# 2_RS485_RS422.net
KiCad netlist of a schematic drawn in EAGLE
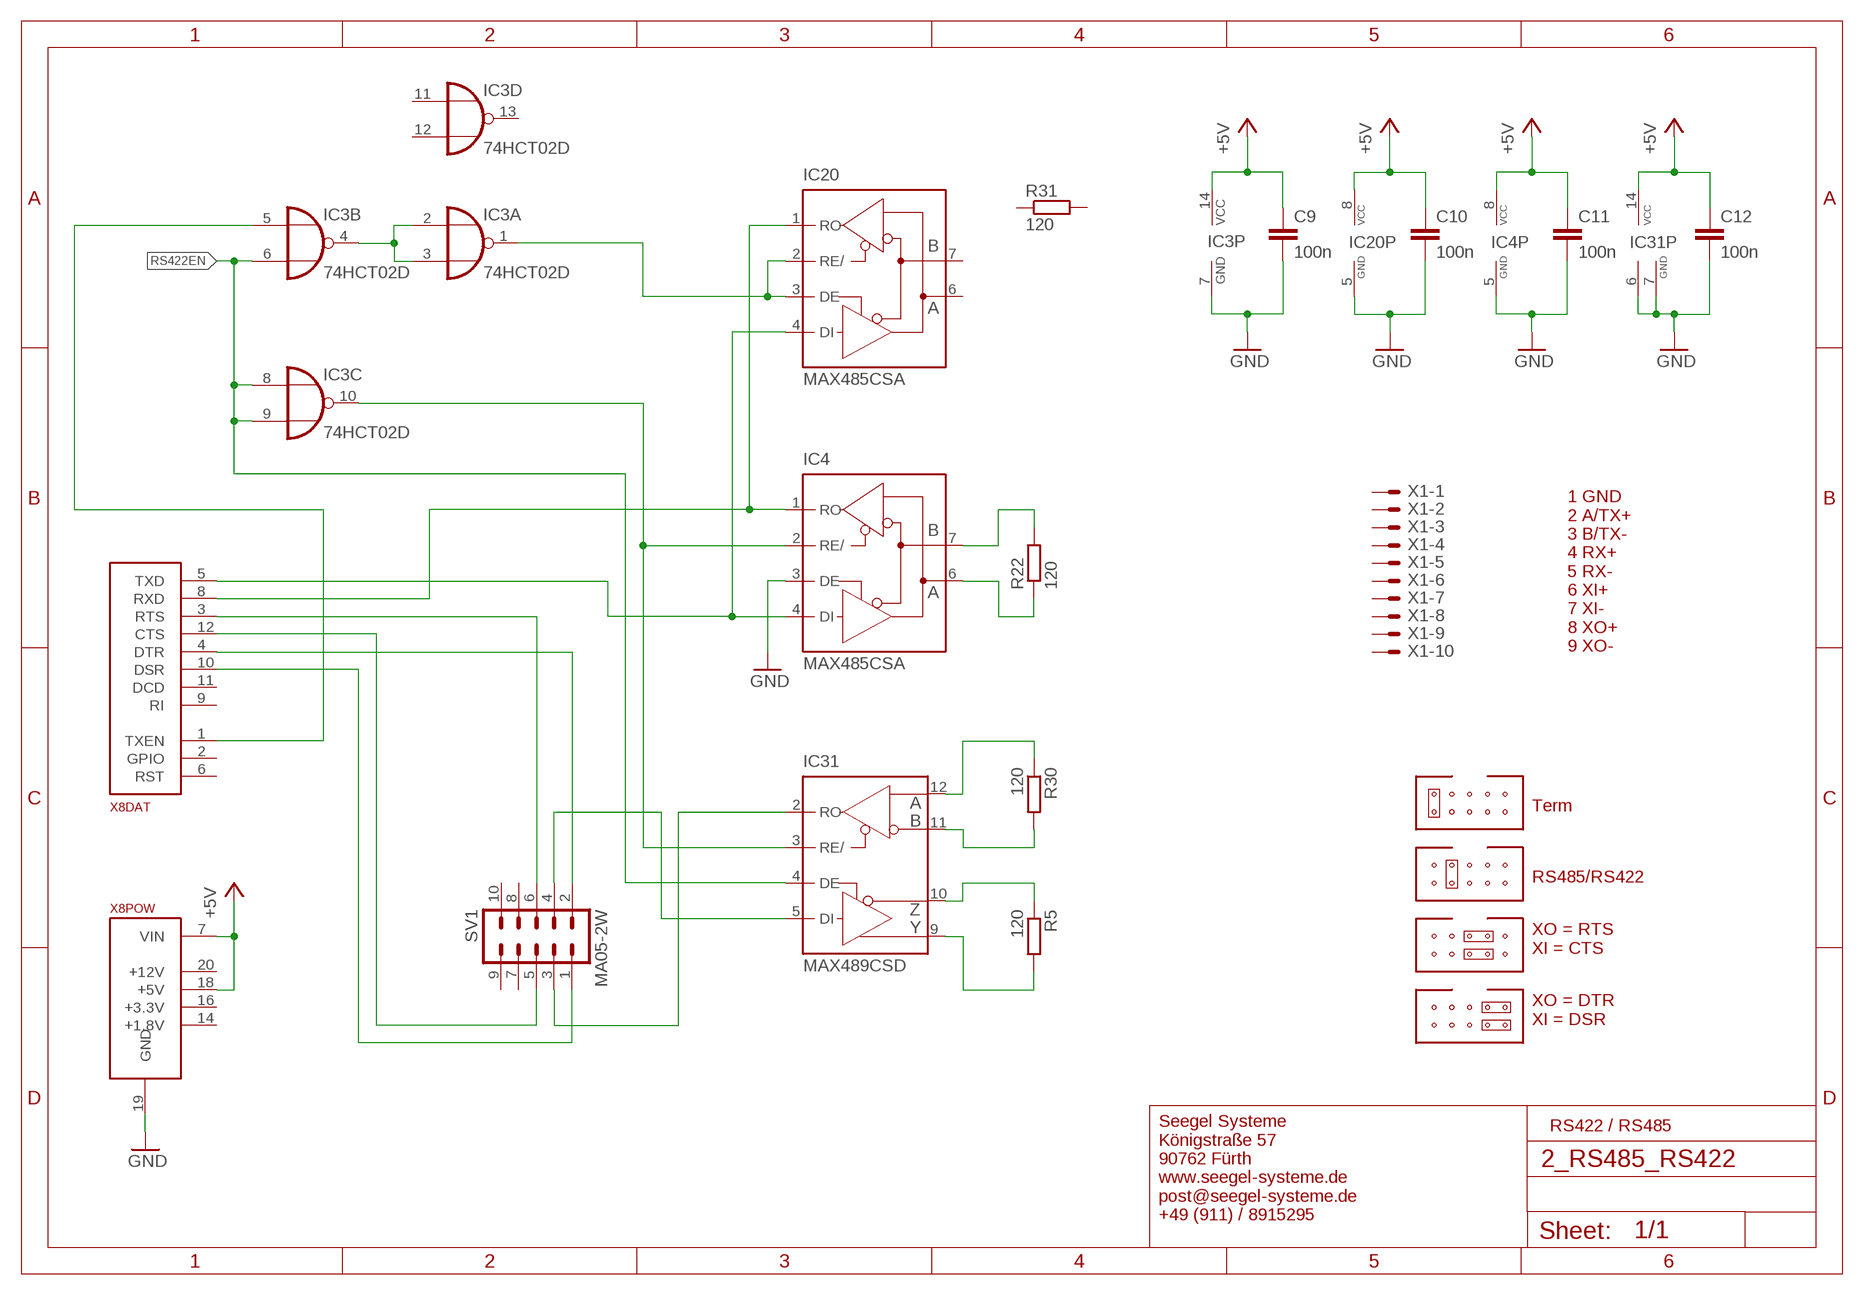
[diagram p0: schematic, sheet 1]

(export (version "E")
  (design (tool "Eeschema 10.0.6"))
  (components
    (comp (ref "C9")
      (value "100n")
      (footprint "eagle-import:C0805")
      (libsource (lib "eagle-import") (part "C-EUC0805"))
    )
    (comp (ref "C10")
      (value "100n")
      (footprint "eagle-import:C0805")
      (libsource (lib "eagle-import") (part "C-EUC0805"))
    )
    (comp (ref "C11")
      (value "100n")
      (footprint "eagle-import:C0805")
      (libsource (lib "eagle-import") (part "C-EUC0805"))
    )
    (comp (ref "C12")
      (value "100n")
      (footprint "eagle-import:C0805")
      (libsource (lib "eagle-import") (part "C-EUC0805"))
    )
    (comp (ref "IC3")
      (value "74HCT02D")
      (footprint "eagle-import:SO14")
      (libsource (lib "eagle-import") (part "7402DHCT"))
    )
    (comp (ref "IC4")
      (value "MAX485CSA")
      (footprint "eagle-import:SO08")
      (fields (field (name "MF") "MAXIM") (field (name "MPN") "MAX481CSA"))
      (libsource (lib "eagle-import") (part "MAX481CSA"))
    )
    (comp (ref "IC20")
      (value "MAX485CSA")
      (footprint "eagle-import:SO08")
      (fields (field (name "MF") "MAXIM") (field (name "MPN") "MAX481CSA"))
      (libsource (lib "eagle-import") (part "MAX481CSA"))
    )
    (comp (ref "IC31")
      (value "MAX489CSD")
      (footprint "eagle-import:SO14")
      (fields (field (name "MF") "MAXIM"))
      (libsource (lib "eagle-import") (part "MAX489CSD"))
    )
    (comp (ref "R5")
      (value "120")
      (footprint "eagle-import:R0805")
      (libsource (lib "eagle-import") (part "R-EU_R0805"))
    )
    (comp (ref "R22")
      (value "120")
      (footprint "eagle-import:R0805")
      (libsource (lib "eagle-import") (part "R-EU_R0805"))
    )
    (comp (ref "R30")
      (value "120")
      (footprint "eagle-import:R0805")
      (libsource (lib "eagle-import") (part "R-EU_R0805"))
    )
    (comp (ref "R31")
      (value "120")
      (footprint "eagle-import:R0805")
      (libsource (lib "eagle-import") (part "R-EU_R0805"))
    )
    (comp (ref "SV1")
      (value "MA05-2W")
      (footprint "eagle-import:MA05-2W")
      (libsource (lib "eagle-import") (part "MA05-2W"))
    )
    (comp (ref "X1")
      (value "AKL18X-10W")
      (footprint "eagle-import:AKL182-10")
      (libsource (lib "eagle-import") (part "AKL18X-10W"))
    )
    (comp (ref "X8")
      (value "ALLSERIALD")
      (footprint "eagle-import:DAUGHTER-THT")
      (libsource (lib "eagle-import") (part "ALLSERIALD"))
    )
  )
  (nets
    (net (code "1") (name "+5V") (class "Default")
      (node (ref "C10") (pin "1") (pinfunction "1_1") (pintype "passive"))
      (node (ref "C11") (pin "1") (pinfunction "1_1") (pintype "passive"))
      (node (ref "C12") (pin "1") (pinfunction "1_1") (pintype "passive"))
      (node (ref "C9") (pin "1") (pinfunction "1_1") (pintype "passive"))
      (node (ref "IC20") (pin "8") (pinfunction "VCC_8") (pintype "power_in"))
      (node (ref "IC3") (pin "14") (pinfunction "VCC_14") (pintype "power_in"))
      (node (ref "IC31") (pin "14") (pinfunction "VCC_14") (pintype "power_in"))
      (node (ref "IC4") (pin "8") (pinfunction "VCC_8") (pintype "power_in"))
      (node (ref "X8") (pin "18") (pinfunction "+5V_18") (pintype "bidirectional"))
      (node (ref "X8") (pin "7") (pinfunction "VIN_7") (pintype "bidirectional"))
    )
    (net (code "2") (name "GND") (class "Default")
      (node (ref "C10") (pin "2") (pinfunction "2_2") (pintype "passive"))
      (node (ref "C11") (pin "2") (pinfunction "2_2") (pintype "passive"))
      (node (ref "C12") (pin "2") (pinfunction "2_2") (pintype "passive"))
      (node (ref "C9") (pin "2") (pinfunction "2_2") (pintype "passive"))
      (node (ref "IC20") (pin "5") (pinfunction "GND_5") (pintype "power_in"))
      (node (ref "IC3") (pin "7") (pinfunction "GND_7") (pintype "power_in"))
      (node (ref "IC31") (pin "6") (pinfunction "GND_6") (pintype "power_in"))
      (node (ref "IC31") (pin "7") (pinfunction "GND_7") (pintype "power_in"))
      (node (ref "IC4") (pin "3") (pinfunction "DE_3") (pintype "input"))
      (node (ref "IC4") (pin "5") (pinfunction "GND_5") (pintype "power_in"))
      (node (ref "X8") (pin "19") (pinfunction "GND_19") (pintype "bidirectional"))
    )
    (net (code "3") (name "Net-(IC3A-I0)") (class "Default")
      (node (ref "IC3") (pin "2") (pinfunction "I0_2") (pintype "input"))
      (node (ref "IC3") (pin "3") (pinfunction "I1_3") (pintype "input"))
      (node (ref "IC3") (pin "4") (pinfunction "O_4") (pintype "output"))
    )
    (net (code "4") (name "Net-(IC3B-I0)") (class "Default")
      (node (ref "IC3") (pin "5") (pinfunction "I0_5") (pintype "input"))
      (node (ref "X8") (pin "1") (pinfunction "TXEN_1") (pintype "bidirectional"))
    )
    (net (code "5") (name "Net-(IC4A-A)") (class "Default")
      (node (ref "IC4") (pin "6") (pinfunction "A_6") (pintype "passive"))
      (node (ref "R22") (pin "1") (pinfunction "1_1") (pintype "passive"))
    )
    (net (code "6") (name "Net-(IC4A-B)") (class "Default")
      (node (ref "IC4") (pin "7") (pinfunction "B_7") (pintype "passive"))
      (node (ref "R22") (pin "2") (pinfunction "2_2") (pintype "passive"))
    )
    (net (code "7") (name "Net-(IC20A-DE)") (class "Default")
      (node (ref "IC20") (pin "2") (pinfunction "RE/_2") (pintype "input"))
      (node (ref "IC20") (pin "3") (pinfunction "DE_3") (pintype "input"))
      (node (ref "IC3") (pin "1") (pinfunction "O_1") (pintype "output"))
    )
    (net (code "8") (name "Net-(IC20A-DI)") (class "Default")
      (node (ref "IC20") (pin "4") (pinfunction "DI_4") (pintype "input"))
      (node (ref "IC4") (pin "4") (pinfunction "DI_4") (pintype "input"))
      (node (ref "X8") (pin "5") (pinfunction "TXD_5") (pintype "bidirectional"))
    )
    (net (code "9") (name "Net-(IC20A-RO)") (class "Default")
      (node (ref "IC20") (pin "1") (pinfunction "RO_1") (pintype "output"))
      (node (ref "IC4") (pin "1") (pinfunction "RO_1") (pintype "output"))
      (node (ref "X8") (pin "8") (pinfunction "RXD_8") (pintype "bidirectional"))
    )
    (net (code "10") (name "Net-(IC31D-A)") (class "Default")
      (node (ref "IC31") (pin "12") (pinfunction "A_12") (pintype "passive"))
      (node (ref "R30") (pin "1") (pinfunction "1_1") (pintype "passive"))
    )
    (net (code "11") (name "Net-(IC31D-B)") (class "Default")
      (node (ref "IC31") (pin "11") (pinfunction "B_11") (pintype "passive"))
      (node (ref "R30") (pin "2") (pinfunction "2_2") (pintype "passive"))
    )
    (net (code "12") (name "Net-(IC31D-DI)") (class "Default")
      (node (ref "IC31") (pin "5") (pinfunction "DI_5") (pintype "input"))
      (node (ref "SV1") (pin "4") (pinfunction "4_4") (pintype "passive"))
    )
    (net (code "13") (name "Net-(IC31D-RE{slash})") (class "Default")
      (node (ref "IC3") (pin "10") (pinfunction "O_10") (pintype "output"))
      (node (ref "IC31") (pin "3") (pinfunction "RE/_3") (pintype "input"))
      (node (ref "IC4") (pin "2") (pinfunction "RE/_2") (pintype "input"))
    )
    (net (code "14") (name "Net-(IC31D-RO)") (class "Default")
      (node (ref "IC31") (pin "2") (pinfunction "RO_2") (pintype "output"))
      (node (ref "SV1") (pin "3") (pinfunction "3_3") (pintype "passive"))
    )
    (net (code "15") (name "Net-(IC31D-Y)") (class "Default")
      (node (ref "IC31") (pin "9") (pinfunction "Y_9") (pintype "passive"))
      (node (ref "R5") (pin "2") (pinfunction "2_2") (pintype "passive"))
    )
    (net (code "16") (name "Net-(IC31D-Z)") (class "Default")
      (node (ref "IC31") (pin "10") (pinfunction "Z_10") (pintype "passive"))
      (node (ref "R5") (pin "1") (pinfunction "1_1") (pintype "passive"))
    )
    (net (code "17") (name "Net-(X8A-CTS)") (class "Default")
      (node (ref "SV1") (pin "5") (pinfunction "5_5") (pintype "passive"))
      (node (ref "X8") (pin "12") (pinfunction "CTS_12") (pintype "bidirectional"))
    )
    (net (code "18") (name "Net-(X8A-DSR)") (class "Default")
      (node (ref "SV1") (pin "1") (pinfunction "1_1") (pintype "passive"))
      (node (ref "X8") (pin "10") (pinfunction "DSR_10") (pintype "bidirectional"))
    )
    (net (code "19") (name "Net-(X8A-DTR)") (class "Default")
      (node (ref "SV1") (pin "2") (pinfunction "2_2") (pintype "passive"))
      (node (ref "X8") (pin "4") (pinfunction "DTR_4") (pintype "bidirectional"))
    )
    (net (code "20") (name "Net-(X8A-RTS)") (class "Default")
      (node (ref "SV1") (pin "6") (pinfunction "6_6") (pintype "passive"))
      (node (ref "X8") (pin "3") (pinfunction "RTS_3") (pintype "bidirectional"))
    )
    (net (code "21") (name "RS422EN") (class "Default")
      (node (ref "IC3") (pin "6") (pinfunction "I1_6") (pintype "input"))
      (node (ref "IC3") (pin "8") (pinfunction "I0_8") (pintype "input"))
      (node (ref "IC3") (pin "9") (pinfunction "I1_9") (pintype "input"))
      (node (ref "IC31") (pin "4") (pinfunction "DE_4") (pintype "input"))
    )
    (net (code "22") (name "unconnected-(IC3D-I0-Pad11)") (class "Default")
      (node (ref "IC3") (pin "11") (pinfunction "I0_11") (pintype "input"))
    )
    (net (code "23") (name "unconnected-(IC3D-I1-Pad12)") (class "Default")
      (node (ref "IC3") (pin "12") (pinfunction "I1_12") (pintype "input"))
    )
    (net (code "24") (name "unconnected-(IC3D-O-Pad13)") (class "Default")
      (node (ref "IC3") (pin "13") (pinfunction "O_13") (pintype "output"))
    )
    (net (code "25") (name "unconnected-(IC20A-A-Pad6)") (class "Default")
      (node (ref "IC20") (pin "6") (pinfunction "A_6") (pintype "passive"))
    )
    (net (code "26") (name "unconnected-(IC20A-B-Pad7)") (class "Default")
      (node (ref "IC20") (pin "7") (pinfunction "B_7") (pintype "passive"))
    )
    (net (code "27") (name "unconnected-(R31-Pad1)") (class "Default")
      (node (ref "R31") (pin "1") (pinfunction "1_1") (pintype "passive"))
    )
    (net (code "28") (name "unconnected-(R31-Pad2)") (class "Default")
      (node (ref "R31") (pin "2") (pinfunction "2_2") (pintype "passive"))
    )
    (net (code "29") (name "unconnected-(SV1-Pad7)") (class "Default")
      (node (ref "SV1") (pin "7") (pinfunction "7_7") (pintype "passive"))
    )
    (net (code "30") (name "unconnected-(SV1-Pad8)") (class "Default")
      (node (ref "SV1") (pin "8") (pinfunction "8_8") (pintype "passive"))
    )
    (net (code "31") (name "unconnected-(SV1-Pad9)") (class "Default")
      (node (ref "SV1") (pin "9") (pinfunction "9_9") (pintype "passive"))
    )
    (net (code "32") (name "unconnected-(SV1-Pad10)") (class "Default")
      (node (ref "SV1") (pin "10") (pinfunction "10_10") (pintype "passive"))
    )
    (net (code "33") (name "unconnected-(X1A-S-PadP$1)") (class "Default")
      (node (ref "X1") (pin "P$1") (pinfunction "S_P$1") (pintype "passive"))
    )
    (net (code "34") (name "unconnected-(X1B-S-PadP$10)") (class "Default")
      (node (ref "X1") (pin "P$10") (pinfunction "S_P$10") (pintype "passive"))
    )
    (net (code "35") (name "unconnected-(X1C-S-PadP$2)") (class "Default")
      (node (ref "X1") (pin "P$2") (pinfunction "S_P$2") (pintype "passive"))
    )
    (net (code "36") (name "unconnected-(X1D-S-PadP$3)") (class "Default")
      (node (ref "X1") (pin "P$3") (pinfunction "S_P$3") (pintype "passive"))
    )
    (net (code "37") (name "unconnected-(X1E-S-PadP$4)") (class "Default")
      (node (ref "X1") (pin "P$4") (pinfunction "S_P$4") (pintype "passive"))
    )
    (net (code "38") (name "unconnected-(X1F-S-PadP$5)") (class "Default")
      (node (ref "X1") (pin "P$5") (pinfunction "S_P$5") (pintype "passive"))
    )
    (net (code "39") (name "unconnected-(X1G-S-PadP$6)") (class "Default")
      (node (ref "X1") (pin "P$6") (pinfunction "S_P$6") (pintype "passive"))
    )
    (net (code "40") (name "unconnected-(X1H-S-PadP$7)") (class "Default")
      (node (ref "X1") (pin "P$7") (pinfunction "S_P$7") (pintype "passive"))
    )
    (net (code "41") (name "unconnected-(X1I-S-PadP$8)") (class "Default")
      (node (ref "X1") (pin "P$8") (pinfunction "S_P$8") (pintype "passive"))
    )
    (net (code "42") (name "unconnected-(X1J-S-PadP$9)") (class "Default")
      (node (ref "X1") (pin "P$9") (pinfunction "S_P$9") (pintype "passive"))
    )
    (net (code "43") (name "unconnected-(X8A-DCD-Pad11)") (class "Default")
      (node (ref "X8") (pin "11") (pinfunction "DCD_11") (pintype "bidirectional"))
    )
    (net (code "44") (name "unconnected-(X8A-GPIO-Pad2)") (class "Default")
      (node (ref "X8") (pin "2") (pinfunction "GPIO_2") (pintype "bidirectional"))
    )
    (net (code "45") (name "unconnected-(X8A-RI-Pad9)") (class "Default")
      (node (ref "X8") (pin "9") (pinfunction "RI_9") (pintype "bidirectional"))
    )
    (net (code "46") (name "unconnected-(X8A-RST-Pad6)") (class "Default")
      (node (ref "X8") (pin "6") (pinfunction "RST_6") (pintype "bidirectional"))
    )
    (net (code "47") (name "unconnected-(X8B-+1.8V-Pad14)") (class "Default")
      (node (ref "X8") (pin "14") (pinfunction "+1.8V_14") (pintype "bidirectional"))
    )
    (net (code "48") (name "unconnected-(X8B-+3.3V-Pad16)") (class "Default")
      (node (ref "X8") (pin "16") (pinfunction "+3.3V_16") (pintype "bidirectional"))
    )
    (net (code "49") (name "unconnected-(X8B-+12V-Pad20)") (class "Default")
      (node (ref "X8") (pin "20") (pinfunction "+12V_20") (pintype "bidirectional"))
    )
  )
)
